# v3c.net
KiCad netlist of a schematic drawn in EAGLE
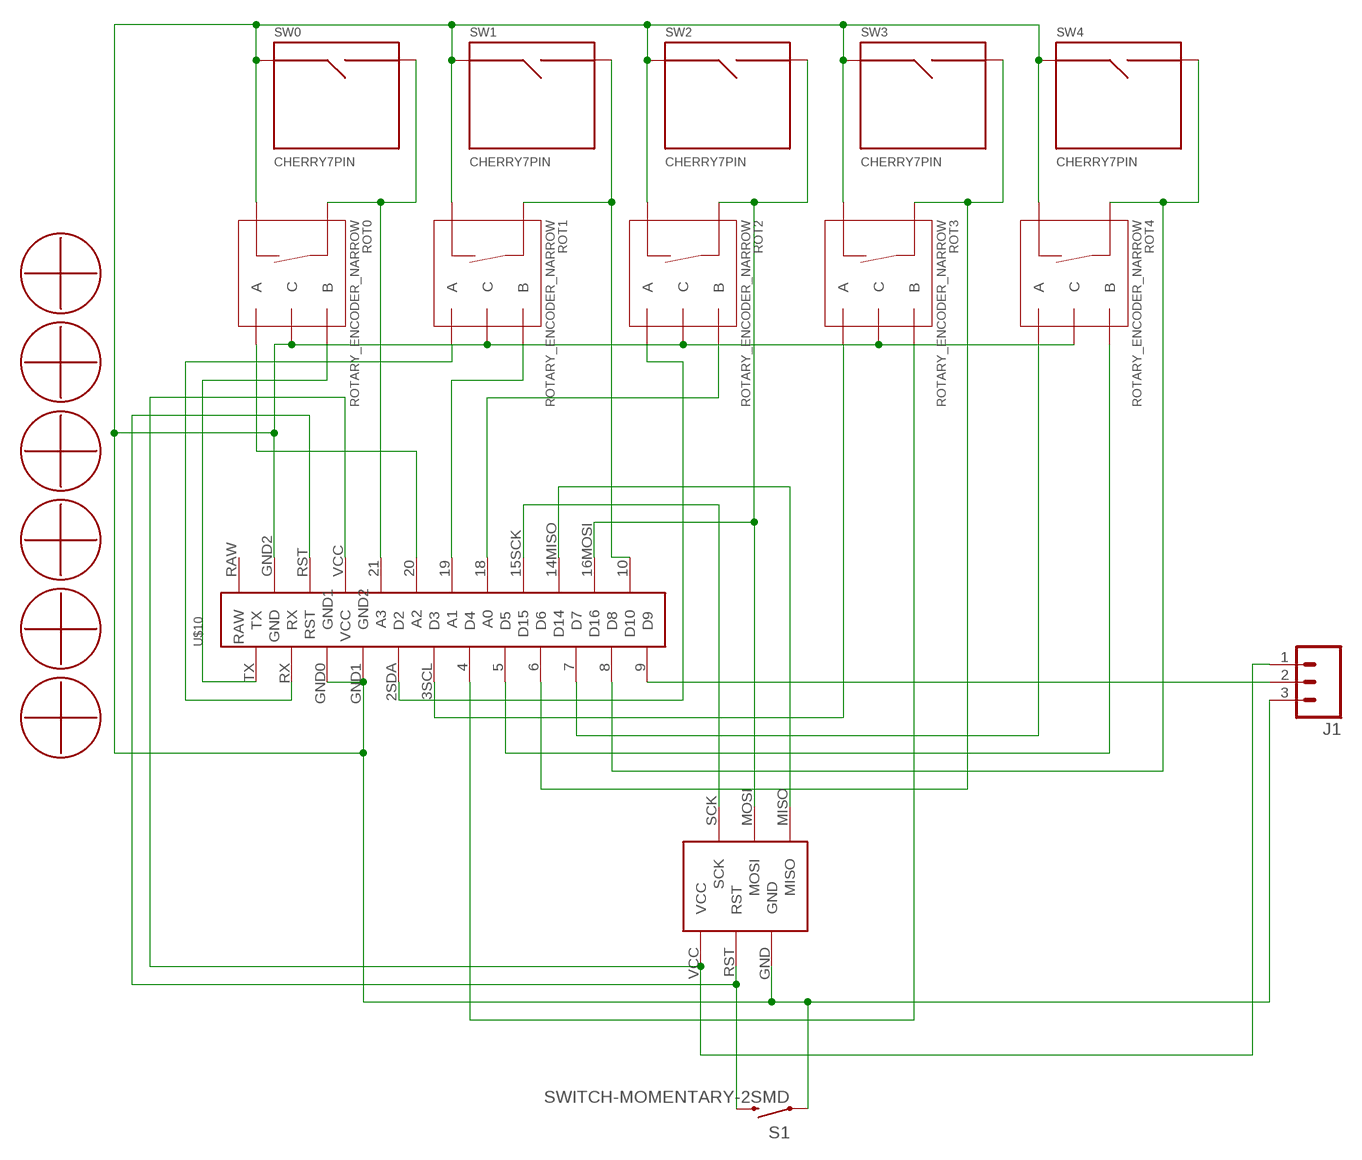
[diagram p0: schematic, sheet 1]

(export (version "E")
  (design (tool "Eeschema 10.0.6"))
  (components
    (comp (ref "J1")
      (value "M031X03_NO_SILK")
      (footprint "eagle-import:1X03_NO_SILK")
      (libsource (lib "eagle-import") (part "M031X03_NO_SILK"))
    )
    (comp (ref "ROT0")
      (value "ROTARY_ENCODER_NARROW")
      (footprint "eagle-import:ROTARY_ENC_NARROW")
      (libsource (lib "eagle-import") (part "ROTARY_ENCODER_NARROW"))
    )
    (comp (ref "ROT1")
      (value "ROTARY_ENCODER_NARROW")
      (footprint "eagle-import:ROTARY_ENC_NARROW")
      (libsource (lib "eagle-import") (part "ROTARY_ENCODER_NARROW"))
    )
    (comp (ref "ROT2")
      (value "ROTARY_ENCODER_NARROW")
      (footprint "eagle-import:ROTARY_ENC_NARROW")
      (libsource (lib "eagle-import") (part "ROTARY_ENCODER_NARROW"))
    )
    (comp (ref "ROT3")
      (value "ROTARY_ENCODER_NARROW")
      (footprint "eagle-import:ROTARY_ENC_NARROW")
      (libsource (lib "eagle-import") (part "ROTARY_ENCODER_NARROW"))
    )
    (comp (ref "ROT4")
      (value "ROTARY_ENCODER_NARROW")
      (footprint "eagle-import:ROTARY_ENC_NARROW")
      (libsource (lib "eagle-import") (part "ROTARY_ENCODER_NARROW"))
    )
    (comp (ref "S1")
      (value "SWITCH-MOMENTARY-2SMD")
      (footprint "eagle-import:TACTILE_SWITCH_SMD")
      (libsource (lib "eagle-import") (part "SWITCH-MOMENTARY-2SMD"))
    )
    (comp (ref "SW0")
      (value "CHERRY7PIN")
      (footprint "eagle-import:CHERRY5HOLE")
      (libsource (lib "eagle-import") (part "CHERRY7PIN"))
    )
    (comp (ref "SW1")
      (value "CHERRY7PIN")
      (footprint "eagle-import:CHERRY5HOLE")
      (libsource (lib "eagle-import") (part "CHERRY7PIN"))
    )
    (comp (ref "SW2")
      (value "CHERRY7PIN")
      (footprint "eagle-import:CHERRY5HOLE")
      (libsource (lib "eagle-import") (part "CHERRY7PIN"))
    )
    (comp (ref "SW3")
      (value "CHERRY7PIN")
      (footprint "eagle-import:CHERRY5HOLE")
      (libsource (lib "eagle-import") (part "CHERRY7PIN"))
    )
    (comp (ref "SW4")
      (value "CHERRY7PIN")
      (footprint "eagle-import:CHERRY5HOLE")
      (libsource (lib "eagle-import") (part "CHERRY7PIN"))
    )
    (comp (ref "U$1")
      (value "ICSP")
      (footprint "eagle-import:ICSP")
      (libsource (lib "eagle-import") (part "ICSP"))
    )
    (comp (ref "U$2")
      (value "M2MOUNT")
      (footprint "eagle-import:M2MOUNT")
      (libsource (lib "eagle-import") (part "M2MOUNT"))
    )
    (comp (ref "U$3")
      (value "M2MOUNT")
      (footprint "eagle-import:M2MOUNT")
      (libsource (lib "eagle-import") (part "M2MOUNT"))
    )
    (comp (ref "U$10")
      (value "PROMICROLOCK")
      (footprint "eagle-import:PROMICRO-LOCK")
      (libsource (lib "eagle-import") (part "PROMICROLOCK"))
    )
    (comp (ref "U$12")
      (value "M2MOUNT")
      (footprint "eagle-import:M2MOUNT")
      (libsource (lib "eagle-import") (part "M2MOUNT"))
    )
    (comp (ref "U$13")
      (value "M2MOUNT")
      (footprint "eagle-import:M2MOUNT")
      (libsource (lib "eagle-import") (part "M2MOUNT"))
    )
    (comp (ref "U$15")
      (value "M2MOUNT")
      (footprint "eagle-import:M2MOUNT")
      (libsource (lib "eagle-import") (part "M2MOUNT"))
    )
    (comp (ref "U$17")
      (value "M2MOUNT")
      (footprint "eagle-import:M2MOUNT")
      (libsource (lib "eagle-import") (part "M2MOUNT"))
    )
  )
  (nets
    (net (code "1") (name "Net-(J1-Pad1)") (class "Default")
      (node (ref "J1") (pin "1") (pinfunction "1_1") (pintype "passive"))
      (node (ref "U$1") (pin "VCC") (pinfunction "VCC_VCC") (pintype "bidirectional"))
      (node (ref "U$10") (pin "VCC") (pinfunction "VCC_VCC") (pintype "bidirectional"))
    )
    (net (code "2") (name "Net-(ROT0-PadB)") (class "Default")
      (node (ref "ROT0") (pin "B") (pinfunction "B_B") (pintype "bidirectional"))
      (node (ref "U$10") (pin "TX") (pinfunction "TX_TX") (pintype "bidirectional"))
    )
    (net (code "3") (name "Net-(ROT1-PadA)") (class "Default")
      (node (ref "ROT1") (pin "A") (pinfunction "A_A") (pintype "bidirectional"))
      (node (ref "U$10") (pin "RX") (pinfunction "RX_RX") (pintype "bidirectional"))
    )
    (net (code "4") (name "Net-(S1-2)") (class "Default")
      (node (ref "S1") (pin "3") (pinfunction "2_3") (pintype "passive"))
      (node (ref "U$1") (pin "RST") (pinfunction "RST_RST") (pintype "bidirectional"))
      (node (ref "U$10") (pin "RST") (pinfunction "RST_RST") (pintype "bidirectional"))
    )
    (net (code "5") (name "Net-(SW0-SIG1)") (class "Default")
      (node (ref "J1") (pin "3") (pinfunction "3_3") (pintype "passive"))
      (node (ref "ROT0") (pin "C") (pinfunction "C_C") (pintype "bidirectional"))
      (node (ref "ROT0") (pin "SW-") (pinfunction "SW-_SW-") (pintype "bidirectional"))
      (node (ref "ROT1") (pin "C") (pinfunction "C_C") (pintype "bidirectional"))
      (node (ref "ROT1") (pin "SW-") (pinfunction "SW-_SW-") (pintype "bidirectional"))
      (node (ref "ROT2") (pin "C") (pinfunction "C_C") (pintype "bidirectional"))
      (node (ref "ROT2") (pin "SW-") (pinfunction "SW-_SW-") (pintype "bidirectional"))
      (node (ref "ROT3") (pin "C") (pinfunction "C_C") (pintype "bidirectional"))
      (node (ref "ROT3") (pin "SW-") (pinfunction "SW-_SW-") (pintype "bidirectional"))
      (node (ref "ROT4") (pin "C") (pinfunction "C_C") (pintype "bidirectional"))
      (node (ref "ROT4") (pin "SW-") (pinfunction "SW-_SW-") (pintype "bidirectional"))
      (node (ref "S1") (pin "1") (pinfunction "1_1") (pintype "passive"))
      (node (ref "SW0") (pin "P$1") (pinfunction "SIG1_P$1") (pintype "bidirectional"))
      (node (ref "SW1") (pin "P$1") (pinfunction "SIG1_P$1") (pintype "bidirectional"))
      (node (ref "SW2") (pin "P$1") (pinfunction "SIG1_P$1") (pintype "bidirectional"))
      (node (ref "SW3") (pin "P$1") (pinfunction "SIG1_P$1") (pintype "bidirectional"))
      (node (ref "SW4") (pin "P$1") (pinfunction "SIG1_P$1") (pintype "bidirectional"))
      (node (ref "U$1") (pin "GND") (pinfunction "GND_GND") (pintype "bidirectional"))
      (node (ref "U$10") (pin "GND0") (pinfunction "GND1_GND0") (pintype "bidirectional"))
      (node (ref "U$10") (pin "GND1") (pinfunction "GND2_GND1") (pintype "bidirectional"))
      (node (ref "U$10") (pin "GND2") (pinfunction "GND_GND2") (pintype "bidirectional"))
    )
    (net (code "6") (name "Net-(SW0-SIG2)") (class "Default")
      (node (ref "ROT0") (pin "SW+") (pinfunction "SW+_SW+") (pintype "bidirectional"))
      (node (ref "SW0") (pin "P$2") (pinfunction "SIG2_P$2") (pintype "bidirectional"))
      (node (ref "U$10") (pin "21") (pinfunction "A3_21") (pintype "bidirectional"))
    )
    (net (code "7") (name "Net-(SW1-SIG2)") (class "Default")
      (node (ref "ROT1") (pin "SW+") (pinfunction "SW+_SW+") (pintype "bidirectional"))
      (node (ref "SW1") (pin "P$2") (pinfunction "SIG2_P$2") (pintype "bidirectional"))
      (node (ref "U$10") (pin "10") (pinfunction "D10_10") (pintype "bidirectional"))
    )
    (net (code "8") (name "Net-(SW2-SIG2)") (class "Default")
      (node (ref "ROT2") (pin "SW+") (pinfunction "SW+_SW+") (pintype "bidirectional"))
      (node (ref "SW2") (pin "P$2") (pinfunction "SIG2_P$2") (pintype "bidirectional"))
      (node (ref "U$1") (pin "MOSI") (pinfunction "MOSI_MOSI") (pintype "bidirectional"))
      (node (ref "U$10") (pin "16MOSI") (pinfunction "D16_16MOSI") (pintype "bidirectional"))
    )
    (net (code "9") (name "Net-(SW3-SIG2)") (class "Default")
      (node (ref "ROT3") (pin "SW+") (pinfunction "SW+_SW+") (pintype "bidirectional"))
      (node (ref "SW3") (pin "P$2") (pinfunction "SIG2_P$2") (pintype "bidirectional"))
      (node (ref "U$10") (pin "6") (pinfunction "D6_6") (pintype "bidirectional"))
    )
    (net (code "10") (name "Net-(SW4-SIG2)") (class "Default")
      (node (ref "ROT4") (pin "SW+") (pinfunction "SW+_SW+") (pintype "bidirectional"))
      (node (ref "SW4") (pin "P$2") (pinfunction "SIG2_P$2") (pintype "bidirectional"))
      (node (ref "U$10") (pin "8") (pinfunction "D8_8") (pintype "bidirectional"))
    )
    (net (code "11") (name "Net-(U$10-A0)") (class "Default")
      (node (ref "ROT2") (pin "B") (pinfunction "B_B") (pintype "bidirectional"))
      (node (ref "U$10") (pin "18") (pinfunction "A0_18") (pintype "bidirectional"))
    )
    (net (code "12") (name "Net-(U$10-A1)") (class "Default")
      (node (ref "ROT1") (pin "B") (pinfunction "B_B") (pintype "bidirectional"))
      (node (ref "U$10") (pin "19") (pinfunction "A1_19") (pintype "bidirectional"))
    )
    (net (code "13") (name "Net-(U$10-A2)") (class "Default")
      (node (ref "ROT0") (pin "A") (pinfunction "A_A") (pintype "bidirectional"))
      (node (ref "U$10") (pin "20") (pinfunction "A2_20") (pintype "bidirectional"))
    )
    (net (code "14") (name "Net-(U$10-D2)") (class "Default")
      (node (ref "ROT2") (pin "A") (pinfunction "A_A") (pintype "bidirectional"))
      (node (ref "U$10") (pin "2SDA") (pinfunction "D2_2SDA") (pintype "bidirectional"))
    )
    (net (code "15") (name "Net-(U$10-D3)") (class "Default")
      (node (ref "ROT3") (pin "A") (pinfunction "A_A") (pintype "bidirectional"))
      (node (ref "U$10") (pin "3SCL") (pinfunction "D3_3SCL") (pintype "bidirectional"))
    )
    (net (code "16") (name "Net-(U$10-D4)") (class "Default")
      (node (ref "ROT3") (pin "B") (pinfunction "B_B") (pintype "bidirectional"))
      (node (ref "U$10") (pin "4") (pinfunction "D4_4") (pintype "bidirectional"))
    )
    (net (code "17") (name "Net-(U$10-D5)") (class "Default")
      (node (ref "ROT4") (pin "B") (pinfunction "B_B") (pintype "bidirectional"))
      (node (ref "U$10") (pin "5") (pinfunction "D5_5") (pintype "bidirectional"))
    )
    (net (code "18") (name "Net-(U$10-D7)") (class "Default")
      (node (ref "ROT4") (pin "A") (pinfunction "A_A") (pintype "bidirectional"))
      (node (ref "U$10") (pin "7") (pinfunction "D7_7") (pintype "bidirectional"))
    )
    (net (code "19") (name "Net-(U$10-D9)") (class "Default")
      (node (ref "J1") (pin "2") (pinfunction "2_2") (pintype "passive"))
      (node (ref "U$10") (pin "9") (pinfunction "D9_9") (pintype "bidirectional"))
    )
    (net (code "20") (name "Net-(U$10-D14)") (class "Default")
      (node (ref "U$1") (pin "MISO") (pinfunction "MISO_MISO") (pintype "bidirectional"))
      (node (ref "U$10") (pin "14MISO") (pinfunction "D14_14MISO") (pintype "bidirectional"))
    )
    (net (code "21") (name "Net-(U$10-D15)") (class "Default")
      (node (ref "U$1") (pin "SCK") (pinfunction "SCK_SCK") (pintype "bidirectional"))
      (node (ref "U$10") (pin "15SCK") (pinfunction "D15_15SCK") (pintype "bidirectional"))
    )
    (net (code "22") (name "unconnected-(U$10-PadRAW)") (class "Default")
      (node (ref "U$10") (pin "RAW") (pinfunction "RAW_RAW") (pintype "bidirectional"))
    )
  )
)
